# usb_input.net
KiCad netlist of a schematic drawn in Altium Designer
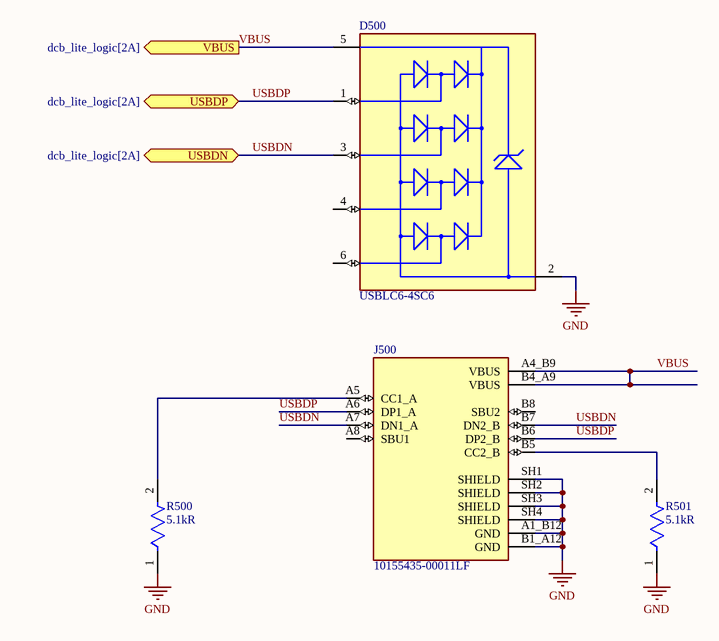
[diagram p0: usb_input.SchDoc]

(export (version "E")
  (design (tool "Eeschema 10.0.6"))
  (components
    (comp (ref "D500")
      (value "USBLC6-4SC6")
      (footprint "FP-SOT23-6L-MFG")
      (description "ESD Suppressor 15KV 6-Pin SOT-23 T/R - Product that comes on tape, but is not reeled")
      (libsource (lib "StackFoundry LLC") (part "3e70b616ccdc4c88b528e1820c4a7da"))
    )
    (comp (ref "J500")
      (value "10155435-00011LF")
      (footprint "AMPHENOL_10155435-00011LF")
      (description "16 Position 5 A USB Right Angle Receptacle Connector")
      (fields (field (name "MF") "Amphenol ICC (FCI)"))
      (libsource (lib "StackFoundry LLC") (part "10155435-00011LF"))
    )
    (comp (ref "R500")
      (value "5.1kR")
      (footprint "FP-AC0402-IPC_A")
      (description "SMD Chip Resistor, 5.1 kOhm, ± 1%, 63 mW, 0402 [1005 Metric], Thick Film, General Purpose")
      (fields (field (name "TOLERANCE") "1%") (field (name "Comment") "AC0402FR-075K1L"))
      (libsource (lib "StackFoundry LLC") (part "1029c3af85768c4190bb7ad29bc67b5"))
    )
    (comp (ref "R501")
      (value "5.1kR")
      (footprint "FP-AC0402-IPC_A")
      (description "SMD Chip Resistor, 5.1 kOhm, ± 1%, 63 mW, 0402 [1005 Metric], Thick Film, General Purpose")
      (fields (field (name "TOLERANCE") "1%") (field (name "Comment") "AC0402FR-075K1L"))
      (libsource (lib "StackFoundry LLC") (part "1029c3af85768c4190bb7ad29bc67b5"))
    )
  )
  (nets
    (net (code "1") (name "/USBDN") (class "Default")
      (node (ref "D500") (pin "3") (pinfunction "I/O2_3") (pintype "bidirectional"))
      (node (ref "J500") (pin "A7") (pinfunction "DN1_A_A7") (pintype "bidirectional"))
      (node (ref "J500") (pin "B7") (pinfunction "DN2_B_B7") (pintype "bidirectional"))
    )
    (net (code "2") (name "/USBDP") (class "Default")
      (node (ref "D500") (pin "1") (pinfunction "I/O1_1") (pintype "bidirectional"))
      (node (ref "J500") (pin "A6") (pinfunction "DP1_A_A6") (pintype "bidirectional"))
      (node (ref "J500") (pin "B6") (pinfunction "DP2_B_B6") (pintype "bidirectional"))
    )
    (net (code "3") (name "/VBUS") (class "Default")
      (node (ref "D500") (pin "5") (pinfunction "VBUS_5") (pintype "power_in"))
      (node (ref "J500") (pin "A4_B9") (pinfunction "VBUS_A4_B9") (pintype "power_in"))
      (node (ref "J500") (pin "B4_A9") (pinfunction "VBUS_B4_A9") (pintype "power_in"))
    )
    (net (code "4") (name "GND") (class "Default")
      (node (ref "D500") (pin "2") (pinfunction "GND_2") (pintype "power_in"))
      (node (ref "J500") (pin "A1_B12") (pinfunction "GND_A1_B12") (pintype "power_in"))
      (node (ref "J500") (pin "B1_A12") (pinfunction "GND_B1_A12") (pintype "power_in"))
      (node (ref "J500") (pin "SH1") (pinfunction "SHIELD_SH1") (pintype "passive"))
      (node (ref "J500") (pin "SH2") (pinfunction "SHIELD_SH2") (pintype "passive"))
      (node (ref "J500") (pin "SH3") (pinfunction "SHIELD_SH3") (pintype "passive"))
      (node (ref "J500") (pin "SH4") (pinfunction "SHIELD_SH4") (pintype "passive"))
      (node (ref "R500") (pin "1") (pinfunction "1_1") (pintype "passive"))
      (node (ref "R501") (pin "1") (pinfunction "1_1") (pintype "passive"))
    )
    (net (code "5") (name "Net-(J500-CC1_A)") (class "Default")
      (node (ref "J500") (pin "A5") (pinfunction "CC1_A_A5") (pintype "bidirectional"))
      (node (ref "R500") (pin "2") (pinfunction "2_2") (pintype "passive"))
    )
    (net (code "6") (name "Net-(J500-CC2_B)") (class "Default")
      (node (ref "J500") (pin "B5") (pinfunction "CC2_B_B5") (pintype "bidirectional"))
      (node (ref "R501") (pin "2") (pinfunction "2_2") (pintype "passive"))
    )
    (net (code "7") (name "unconnected-(D500-I{slash}O3-Pad4)") (class "Default")
      (node (ref "D500") (pin "4") (pinfunction "I/O3_4") (pintype "bidirectional"))
    )
    (net (code "8") (name "unconnected-(D500-I{slash}O4-Pad6)") (class "Default")
      (node (ref "D500") (pin "6") (pinfunction "I/O4_6") (pintype "bidirectional"))
    )
    (net (code "9") (name "unconnected-(J500-SBU1-PadA8)") (class "Default")
      (node (ref "J500") (pin "A8") (pinfunction "SBU1_A8") (pintype "bidirectional"))
    )
    (net (code "10") (name "unconnected-(J500-SBU2-PadB8)") (class "Default")
      (node (ref "J500") (pin "B8") (pinfunction "SBU2_B8") (pintype "bidirectional"))
    )
  )
)
